# MRF24J40MA_Breakout_verC.net
KiCad netlist of a schematic drawn in EAGLE
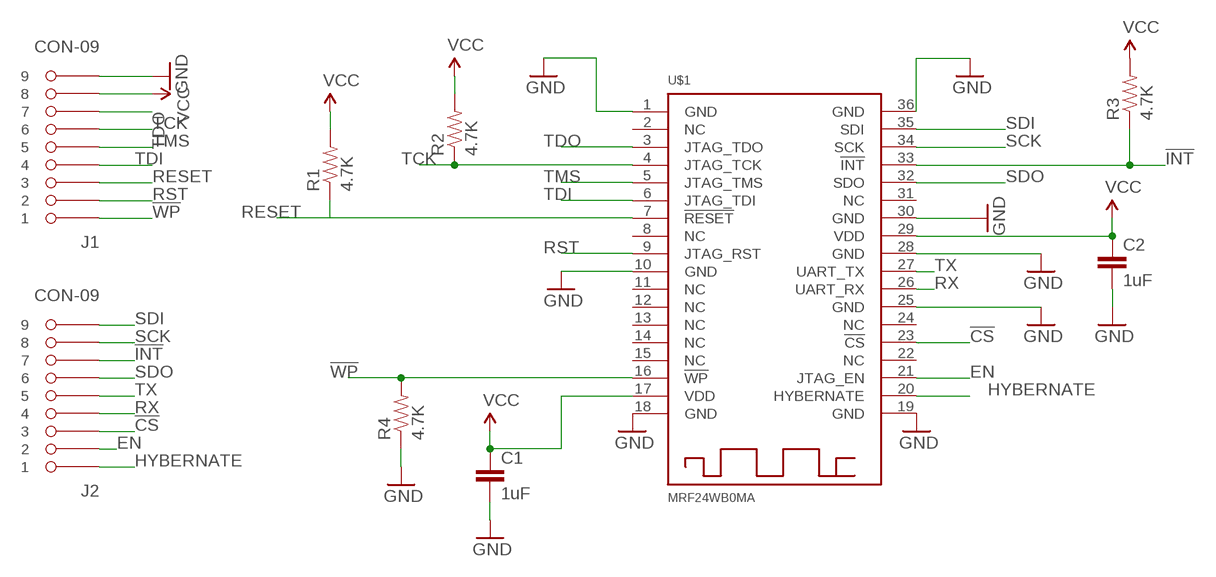
[diagram p0: schematic, sheet 1]

(export (version "E")
  (design (tool "Eeschema 10.0.6"))
  (components
    (comp (ref "C1")
      (value "1uF")
      (footprint "eagle-import:0603-CAP")
      (libsource (lib "eagle-import") (part "CAP0603-CAP"))
    )
    (comp (ref "C2")
      (value "1uF")
      (footprint "eagle-import:0603-CAP")
      (libsource (lib "eagle-import") (part "CAP0603-CAP"))
    )
    (comp (ref "J1")
      (value "CON-09")
      (footprint "eagle-import:09-SMD")
      (libsource (lib "eagle-import") (part "CON-09"))
    )
    (comp (ref "J2")
      (value "CON-09")
      (footprint "eagle-import:09-SMD")
      (libsource (lib "eagle-import") (part "CON-09"))
    )
    (comp (ref "R1")
      (value "4.7K")
      (footprint "eagle-import:0603-RES")
      (libsource (lib "eagle-import") (part "RESISTOR0603-RES"))
    )
    (comp (ref "R2")
      (value "4.7K")
      (footprint "eagle-import:0603-RES")
      (libsource (lib "eagle-import") (part "RESISTOR0603-RES"))
    )
    (comp (ref "R3")
      (value "4.7K")
      (footprint "eagle-import:0603-RES")
      (libsource (lib "eagle-import") (part "RESISTOR0603-RES"))
    )
    (comp (ref "R4")
      (value "4.7K")
      (footprint "eagle-import:0603-RES")
      (libsource (lib "eagle-import") (part "RESISTOR0603-RES"))
    )
    (comp (ref "U$1")
      (value "MRF24WB0MA")
      (footprint "eagle-import:MRF24WB0MA")
      (libsource (lib "eagle-import") (part "MRF24WB0MA"))
    )
  )
  (nets
    (net (code "1") (name "/EN") (class "Default")
      (node (ref "J2") (pin "2") (pinfunction "2_2") (pintype "bidirectional"))
      (node (ref "U$1") (pin "21") (pinfunction "JTAG_EN_21") (pintype "bidirectional"))
    )
    (net (code "2") (name "/HYBERNATE") (class "Default")
      (node (ref "J2") (pin "1") (pinfunction "1_1") (pintype "bidirectional"))
      (node (ref "U$1") (pin "20") (pinfunction "HYBERNATE_20") (pintype "bidirectional"))
    )
    (net (code "3") (name "/RESET") (class "Default")
      (node (ref "J1") (pin "3") (pinfunction "3_3") (pintype "bidirectional"))
      (node (ref "R1") (pin "1") (pinfunction "1_1") (pintype "passive"))
      (node (ref "U$1") (pin "7") (pinfunction "~{RESET}_7") (pintype "bidirectional"))
    )
    (net (code "4") (name "/RST") (class "Default")
      (node (ref "J1") (pin "2") (pinfunction "2_2") (pintype "bidirectional"))
      (node (ref "U$1") (pin "9") (pinfunction "JTAG_RST_9") (pintype "bidirectional"))
    )
    (net (code "5") (name "/RX") (class "Default")
      (node (ref "J2") (pin "4") (pinfunction "4_4") (pintype "bidirectional"))
      (node (ref "U$1") (pin "26") (pinfunction "UART_RX_26") (pintype "bidirectional"))
    )
    (net (code "6") (name "/SCK") (class "Default")
      (node (ref "J2") (pin "8") (pinfunction "8_8") (pintype "bidirectional"))
      (node (ref "U$1") (pin "34") (pinfunction "SCK_34") (pintype "bidirectional"))
    )
    (net (code "7") (name "/SDI") (class "Default")
      (node (ref "J2") (pin "9") (pinfunction "9_9") (pintype "bidirectional"))
      (node (ref "U$1") (pin "35") (pinfunction "SDI_35") (pintype "bidirectional"))
    )
    (net (code "8") (name "/SDO") (class "Default")
      (node (ref "J2") (pin "6") (pinfunction "6_6") (pintype "bidirectional"))
      (node (ref "U$1") (pin "32") (pinfunction "SDO_32") (pintype "bidirectional"))
    )
    (net (code "9") (name "/TCK") (class "Default")
      (node (ref "J1") (pin "6") (pinfunction "6_6") (pintype "bidirectional"))
      (node (ref "R2") (pin "1") (pinfunction "1_1") (pintype "passive"))
      (node (ref "U$1") (pin "4") (pinfunction "JTAG_TCK_4") (pintype "bidirectional"))
    )
    (net (code "10") (name "/TDI") (class "Default")
      (node (ref "J1") (pin "4") (pinfunction "4_4") (pintype "bidirectional"))
      (node (ref "U$1") (pin "6") (pinfunction "JTAG_TDI_6") (pintype "bidirectional"))
    )
    (net (code "11") (name "/TDO") (class "Default")
      (node (ref "J1") (pin "7") (pinfunction "7_7") (pintype "bidirectional"))
      (node (ref "U$1") (pin "3") (pinfunction "JTAG_TDO_3") (pintype "bidirectional"))
    )
    (net (code "12") (name "/TMS") (class "Default")
      (node (ref "J1") (pin "5") (pinfunction "5_5") (pintype "bidirectional"))
      (node (ref "U$1") (pin "5") (pinfunction "JTAG_TMS_5") (pintype "bidirectional"))
    )
    (net (code "13") (name "/TX") (class "Default")
      (node (ref "J2") (pin "5") (pinfunction "5_5") (pintype "bidirectional"))
      (node (ref "U$1") (pin "27") (pinfunction "UART_TX_27") (pintype "bidirectional"))
    )
    (net (code "14") (name "/~{CS}") (class "Default")
      (node (ref "J2") (pin "3") (pinfunction "3_3") (pintype "bidirectional"))
      (node (ref "U$1") (pin "23") (pinfunction "~{CS}_23") (pintype "bidirectional"))
    )
    (net (code "15") (name "/~{INT}") (class "Default")
      (node (ref "J2") (pin "7") (pinfunction "7_7") (pintype "bidirectional"))
      (node (ref "R3") (pin "1") (pinfunction "1_1") (pintype "passive"))
      (node (ref "U$1") (pin "33") (pinfunction "~{INT}_33") (pintype "bidirectional"))
    )
    (net (code "16") (name "/~{WP}") (class "Default")
      (node (ref "J1") (pin "1") (pinfunction "1_1") (pintype "bidirectional"))
      (node (ref "R4") (pin "2") (pinfunction "2_2") (pintype "passive"))
      (node (ref "U$1") (pin "16") (pinfunction "~{WP}_16") (pintype "bidirectional"))
    )
    (net (code "17") (name "GND") (class "Default")
      (node (ref "C1") (pin "2") (pinfunction "2_2") (pintype "passive"))
      (node (ref "C2") (pin "2") (pinfunction "2_2") (pintype "passive"))
      (node (ref "J1") (pin "9") (pinfunction "9_9") (pintype "bidirectional"))
      (node (ref "R4") (pin "1") (pinfunction "1_1") (pintype "passive"))
      (node (ref "U$1") (pin "1") (pinfunction "GND_1") (pintype "bidirectional"))
      (node (ref "U$1") (pin "10") (pinfunction "GND_10") (pintype "bidirectional"))
      (node (ref "U$1") (pin "18") (pinfunction "GND_18") (pintype "bidirectional"))
      (node (ref "U$1") (pin "19") (pinfunction "GND_19") (pintype "bidirectional"))
      (node (ref "U$1") (pin "25") (pinfunction "GND_25") (pintype "bidirectional"))
      (node (ref "U$1") (pin "28") (pinfunction "GND_28") (pintype "bidirectional"))
      (node (ref "U$1") (pin "30") (pinfunction "GND_30") (pintype "bidirectional"))
      (node (ref "U$1") (pin "36") (pinfunction "GND_36") (pintype "bidirectional"))
    )
    (net (code "18") (name "VCC") (class "Default")
      (node (ref "C1") (pin "1") (pinfunction "1_1") (pintype "passive"))
      (node (ref "C2") (pin "1") (pinfunction "1_1") (pintype "passive"))
      (node (ref "J1") (pin "8") (pinfunction "8_8") (pintype "bidirectional"))
      (node (ref "R1") (pin "2") (pinfunction "2_2") (pintype "passive"))
      (node (ref "R2") (pin "2") (pinfunction "2_2") (pintype "passive"))
      (node (ref "R3") (pin "2") (pinfunction "2_2") (pintype "passive"))
      (node (ref "U$1") (pin "17") (pinfunction "VDD_17") (pintype "bidirectional"))
      (node (ref "U$1") (pin "29") (pinfunction "VDD_29") (pintype "bidirectional"))
    )
    (net (code "19") (name "unconnected-(U$1-NC-Pad2)") (class "Default")
      (node (ref "U$1") (pin "2") (pinfunction "NC_2") (pintype "bidirectional"))
    )
    (net (code "20") (name "unconnected-(U$1-NC-Pad8)") (class "Default")
      (node (ref "U$1") (pin "8") (pinfunction "NC_8") (pintype "bidirectional"))
    )
    (net (code "21") (name "unconnected-(U$1-NC-Pad11)") (class "Default")
      (node (ref "U$1") (pin "11") (pinfunction "NC_11") (pintype "bidirectional"))
    )
    (net (code "22") (name "unconnected-(U$1-NC-Pad12)") (class "Default")
      (node (ref "U$1") (pin "12") (pinfunction "NC_12") (pintype "bidirectional"))
    )
    (net (code "23") (name "unconnected-(U$1-NC-Pad13)") (class "Default")
      (node (ref "U$1") (pin "13") (pinfunction "NC_13") (pintype "bidirectional"))
    )
    (net (code "24") (name "unconnected-(U$1-NC-Pad14)") (class "Default")
      (node (ref "U$1") (pin "14") (pinfunction "NC_14") (pintype "bidirectional"))
    )
    (net (code "25") (name "unconnected-(U$1-NC-Pad15)") (class "Default")
      (node (ref "U$1") (pin "15") (pinfunction "NC_15") (pintype "bidirectional"))
    )
    (net (code "26") (name "unconnected-(U$1-NC-Pad22)") (class "Default")
      (node (ref "U$1") (pin "22") (pinfunction "NC_22") (pintype "bidirectional"))
    )
    (net (code "27") (name "unconnected-(U$1-NC-Pad24)") (class "Default")
      (node (ref "U$1") (pin "24") (pinfunction "NC_24") (pintype "bidirectional"))
    )
    (net (code "28") (name "unconnected-(U$1-NC-Pad31)") (class "Default")
      (node (ref "U$1") (pin "31") (pinfunction "NC_31") (pintype "bidirectional"))
    )
  )
)
